# 13_-_TOP_BOARD_HEADER.net
KiCad netlist of a schematic drawn in Altium Designer
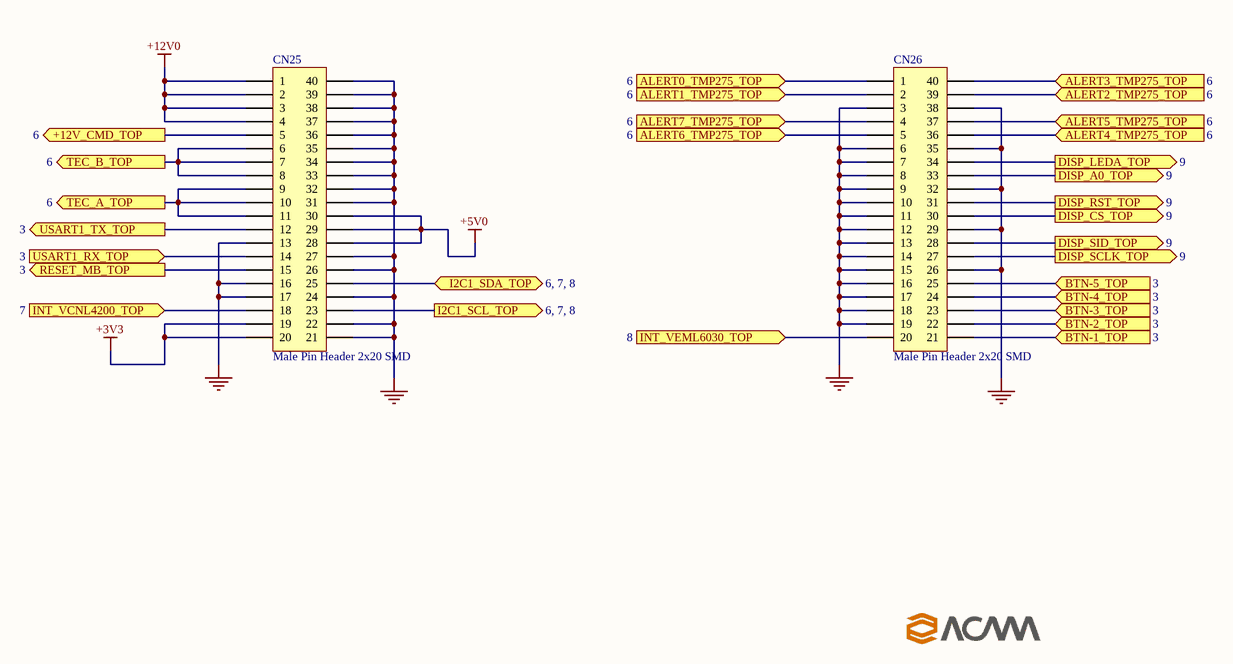
[diagram p0: [13] - TOP BOARD HEADER.SchDoc]

(export (version "E")
  (design (tool "Eeschema 10.0.6"))
  (components
    (comp (ref "CN25")
      (value "Male Pin Header 2x20 SMD")
      (footprint "HEADER_2x20_SMD")
      (description "SMD Male Pin Header 2.54mm Pitch, 2x20")
      (libsource (lib "Farzan Custom Library") (part "Pin header Male 2x20 smd"))
    )
    (comp (ref "CN26")
      (value "Male Pin Header 2x20 SMD")
      (footprint "HEADER_2x20_SMD")
      (description "SMD Male Pin Header 2.54mm Pitch, 2x20")
      (libsource (lib "Farzan Custom Library") (part "Pin header Male 2x20 smd"))
    )
  )
  (nets
    (net (code "1") (name "+3V3") (class "Default")
      (node (ref "CN25") (pin "19") (pinfunction "19_19") (pintype "passive"))
      (node (ref "CN25") (pin "20") (pinfunction "20_20") (pintype "passive"))
    )
    (net (code "2") (name "+5V0") (class "Default")
      (node (ref "CN25") (pin "28") (pinfunction "28_28") (pintype "passive"))
      (node (ref "CN25") (pin "29") (pinfunction "29_29") (pintype "passive"))
      (node (ref "CN25") (pin "30") (pinfunction "30_30") (pintype "passive"))
    )
    (net (code "3") (name "+12V0") (class "Default")
      (node (ref "CN25") (pin "1") (pinfunction "1_1") (pintype "passive"))
      (node (ref "CN25") (pin "2") (pinfunction "2_2") (pintype "passive"))
      (node (ref "CN25") (pin "3") (pinfunction "3_3") (pintype "passive"))
      (node (ref "CN25") (pin "4") (pinfunction "4_4") (pintype "passive"))
    )
    (net (code "4") (name "/+12V_CMD_TOP") (class "Default")
      (node (ref "CN25") (pin "5") (pinfunction "5_5") (pintype "passive"))
    )
    (net (code "5") (name "/ALERT0_TMP275_TOP") (class "Default")
      (node (ref "CN26") (pin "1") (pinfunction "1_1") (pintype "passive"))
    )
    (net (code "6") (name "/ALERT1_TMP275_TOP") (class "Default")
      (node (ref "CN26") (pin "2") (pinfunction "2_2") (pintype "passive"))
    )
    (net (code "7") (name "/ALERT2_TMP275_TOP") (class "Default")
      (node (ref "CN26") (pin "39") (pinfunction "39_39") (pintype "passive"))
    )
    (net (code "8") (name "/ALERT3_TMP275_TOP") (class "Default")
      (node (ref "CN26") (pin "40") (pinfunction "40_40") (pintype "passive"))
    )
    (net (code "9") (name "/ALERT4_TMP275_TOP") (class "Default")
      (node (ref "CN26") (pin "36") (pinfunction "36_36") (pintype "passive"))
    )
    (net (code "10") (name "/ALERT5_TMP275_TOP") (class "Default")
      (node (ref "CN26") (pin "37") (pinfunction "37_37") (pintype "passive"))
    )
    (net (code "11") (name "/ALERT6_TMP275_TOP") (class "Default")
      (node (ref "CN26") (pin "5") (pinfunction "5_5") (pintype "passive"))
    )
    (net (code "12") (name "/ALERT7_TMP275_TOP") (class "Default")
      (node (ref "CN26") (pin "4") (pinfunction "4_4") (pintype "passive"))
    )
    (net (code "13") (name "/BTN-1_TOP") (class "Default")
      (node (ref "CN26") (pin "21") (pinfunction "21_21") (pintype "passive"))
    )
    (net (code "14") (name "/BTN-2_TOP") (class "Default")
      (node (ref "CN26") (pin "22") (pinfunction "22_22") (pintype "passive"))
    )
    (net (code "15") (name "/BTN-3_TOP") (class "Default")
      (node (ref "CN26") (pin "23") (pinfunction "23_23") (pintype "passive"))
    )
    (net (code "16") (name "/BTN-4_TOP") (class "Default")
      (node (ref "CN26") (pin "24") (pinfunction "24_24") (pintype "passive"))
    )
    (net (code "17") (name "/BTN-5_TOP") (class "Default")
      (node (ref "CN26") (pin "25") (pinfunction "25_25") (pintype "passive"))
    )
    (net (code "18") (name "/DISP_A0_TOP") (class "Default")
      (node (ref "CN26") (pin "33") (pinfunction "33_33") (pintype "passive"))
    )
    (net (code "19") (name "/DISP_CS_TOP") (class "Default")
      (node (ref "CN26") (pin "30") (pinfunction "30_30") (pintype "passive"))
    )
    (net (code "20") (name "/DISP_LEDA_TOP") (class "Default")
      (node (ref "CN26") (pin "34") (pinfunction "34_34") (pintype "passive"))
    )
    (net (code "21") (name "/DISP_RST_TOP") (class "Default")
      (node (ref "CN26") (pin "31") (pinfunction "31_31") (pintype "passive"))
    )
    (net (code "22") (name "/DISP_SCLK_TOP") (class "Default")
      (node (ref "CN26") (pin "27") (pinfunction "27_27") (pintype "passive"))
    )
    (net (code "23") (name "/DISP_SID_TOP") (class "Default")
      (node (ref "CN26") (pin "28") (pinfunction "28_28") (pintype "passive"))
    )
    (net (code "24") (name "/I2C1_SCL_TOP") (class "Default")
      (node (ref "CN25") (pin "23") (pinfunction "23_23") (pintype "passive"))
    )
    (net (code "25") (name "/I2C1_SDA_TOP") (class "Default")
      (node (ref "CN25") (pin "25") (pinfunction "25_25") (pintype "passive"))
    )
    (net (code "26") (name "/INT_VCNL4200_TOP") (class "Default")
      (node (ref "CN25") (pin "18") (pinfunction "18_18") (pintype "passive"))
    )
    (net (code "27") (name "/INT_VEML6030_TOP") (class "Default")
      (node (ref "CN26") (pin "20") (pinfunction "20_20") (pintype "passive"))
    )
    (net (code "28") (name "/RESET_MB_TOP") (class "Default")
      (node (ref "CN25") (pin "15") (pinfunction "15_15") (pintype "passive"))
    )
    (net (code "29") (name "/TEC_A_TOP") (class "Default")
      (node (ref "CN25") (pin "10") (pinfunction "10_10") (pintype "passive"))
      (node (ref "CN25") (pin "11") (pinfunction "11_11") (pintype "passive"))
      (node (ref "CN25") (pin "9") (pinfunction "9_9") (pintype "passive"))
    )
    (net (code "30") (name "/TEC_B_TOP") (class "Default")
      (node (ref "CN25") (pin "6") (pinfunction "6_6") (pintype "passive"))
      (node (ref "CN25") (pin "7") (pinfunction "7_7") (pintype "passive"))
      (node (ref "CN25") (pin "8") (pinfunction "8_8") (pintype "passive"))
    )
    (net (code "31") (name "/USART1_RX_TOP") (class "Default")
      (node (ref "CN25") (pin "14") (pinfunction "14_14") (pintype "passive"))
    )
    (net (code "32") (name "/USART1_TX_TOP") (class "Default")
      (node (ref "CN25") (pin "12") (pinfunction "12_12") (pintype "passive"))
    )
    (net (code "33") (name "GND") (class "Default")
      (node (ref "CN25") (pin "13") (pinfunction "13_13") (pintype "passive"))
      (node (ref "CN25") (pin "16") (pinfunction "16_16") (pintype "passive"))
      (node (ref "CN25") (pin "17") (pinfunction "17_17") (pintype "passive"))
      (node (ref "CN25") (pin "21") (pinfunction "21_21") (pintype "passive"))
      (node (ref "CN25") (pin "22") (pinfunction "22_22") (pintype "passive"))
      (node (ref "CN25") (pin "24") (pinfunction "24_24") (pintype "passive"))
      (node (ref "CN25") (pin "26") (pinfunction "26_26") (pintype "passive"))
      (node (ref "CN25") (pin "27") (pinfunction "27_27") (pintype "passive"))
      (node (ref "CN25") (pin "31") (pinfunction "31_31") (pintype "passive"))
      (node (ref "CN25") (pin "32") (pinfunction "32_32") (pintype "passive"))
      (node (ref "CN25") (pin "33") (pinfunction "33_33") (pintype "passive"))
      (node (ref "CN25") (pin "34") (pinfunction "34_34") (pintype "passive"))
      (node (ref "CN25") (pin "35") (pinfunction "35_35") (pintype "passive"))
      (node (ref "CN25") (pin "36") (pinfunction "36_36") (pintype "passive"))
      (node (ref "CN25") (pin "37") (pinfunction "37_37") (pintype "passive"))
      (node (ref "CN25") (pin "38") (pinfunction "38_38") (pintype "passive"))
      (node (ref "CN25") (pin "39") (pinfunction "39_39") (pintype "passive"))
      (node (ref "CN25") (pin "40") (pinfunction "40_40") (pintype "passive"))
      (node (ref "CN26") (pin "10") (pinfunction "10_10") (pintype "passive"))
      (node (ref "CN26") (pin "11") (pinfunction "11_11") (pintype "passive"))
      (node (ref "CN26") (pin "12") (pinfunction "12_12") (pintype "passive"))
      (node (ref "CN26") (pin "13") (pinfunction "13_13") (pintype "passive"))
      (node (ref "CN26") (pin "14") (pinfunction "14_14") (pintype "passive"))
      (node (ref "CN26") (pin "15") (pinfunction "15_15") (pintype "passive"))
      (node (ref "CN26") (pin "16") (pinfunction "16_16") (pintype "passive"))
      (node (ref "CN26") (pin "17") (pinfunction "17_17") (pintype "passive"))
      (node (ref "CN26") (pin "18") (pinfunction "18_18") (pintype "passive"))
      (node (ref "CN26") (pin "19") (pinfunction "19_19") (pintype "passive"))
      (node (ref "CN26") (pin "26") (pinfunction "26_26") (pintype "passive"))
      (node (ref "CN26") (pin "29") (pinfunction "29_29") (pintype "passive"))
      (node (ref "CN26") (pin "3") (pinfunction "3_3") (pintype "passive"))
      (node (ref "CN26") (pin "32") (pinfunction "32_32") (pintype "passive"))
      (node (ref "CN26") (pin "35") (pinfunction "35_35") (pintype "passive"))
      (node (ref "CN26") (pin "38") (pinfunction "38_38") (pintype "passive"))
      (node (ref "CN26") (pin "6") (pinfunction "6_6") (pintype "passive"))
      (node (ref "CN26") (pin "7") (pinfunction "7_7") (pintype "passive"))
      (node (ref "CN26") (pin "8") (pinfunction "8_8") (pintype "passive"))
      (node (ref "CN26") (pin "9") (pinfunction "9_9") (pintype "passive"))
    )
  )
)
